# Morpheus_conector.net
KiCad netlist of a schematic drawn in Altium Designer
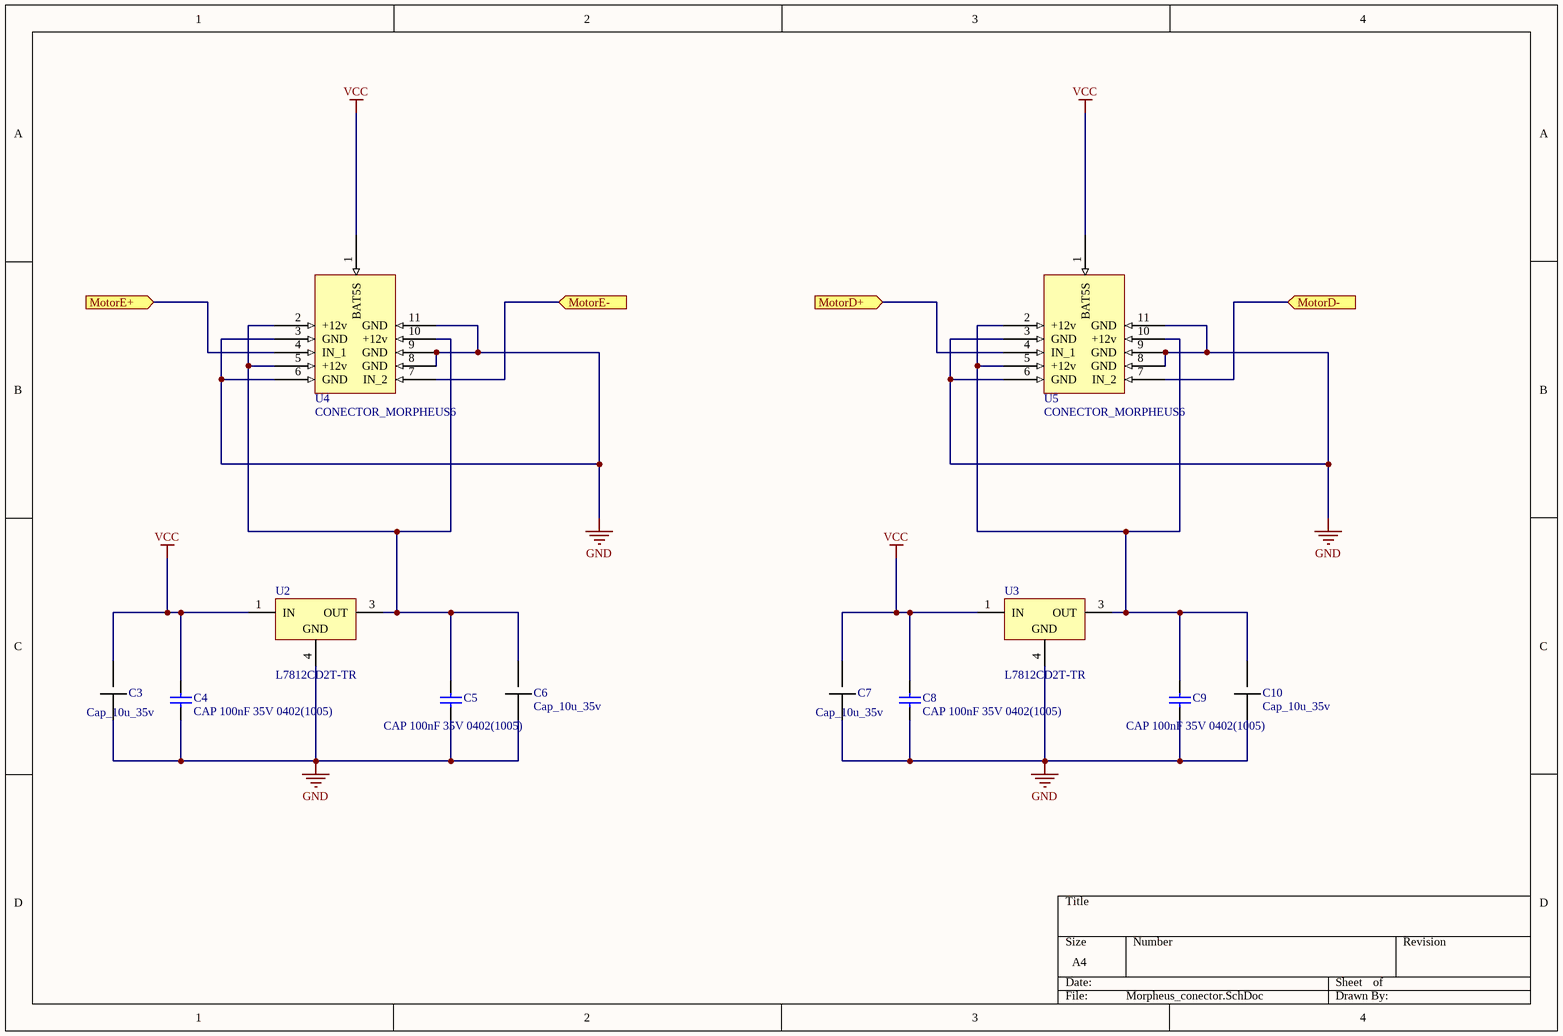
[diagram p0: Morpheus_conector.SchDoc]

(export (version "E")
  (design (tool "Eeschema 10.0.6"))
  (components
    (comp (ref "C3")
      (value "Cap_10u_35v")
      (footprint "Passives:CAP POL 2917/7343")
      (description "80-T491D106M35AT7280")
      (libsource (lib "LibSanhaço2017") (part "Cap_10u_35v"))
    )
    (comp (ref "C4")
      (value "CAP 100nF 35V 0402(1005)")
      (footprint "CAPC0402(1005)60_N")
      (fields (field (name "TOLERANCE") "Â±20%"))
      (libsource (lib "CAP 0402 100nF 35V") (part "CMP-1034-02076-1"))
    )
    (comp (ref "C5")
      (value "CAP 100nF 35V 0402(1005)")
      (footprint "CAPC0402(1005)60_N")
      (fields (field (name "TOLERANCE") "Â±20%"))
      (libsource (lib "CAP 0402 100nF 35V") (part "CMP-1034-02076-1"))
    )
    (comp (ref "C6")
      (value "Cap_10u_35v")
      (footprint "Passives:CAP POL 2917/7343")
      (description "80-T491D106M35AT7280")
      (libsource (lib "LibSanhaço2017") (part "Cap_10u_35v"))
    )
    (comp (ref "C7")
      (value "Cap_10u_35v")
      (footprint "Passives:CAP POL 2917/7343")
      (description "80-T491D106M35AT7280")
      (libsource (lib "LibSanhaço2017") (part "Cap_10u_35v"))
    )
    (comp (ref "C8")
      (value "CAP 100nF 35V 0402(1005)")
      (footprint "CAPC0402(1005)60_N")
      (fields (field (name "TOLERANCE") "Â±20%"))
      (libsource (lib "CAP 0402 100nF 35V") (part "CMP-1034-02076-1"))
    )
    (comp (ref "C9")
      (value "CAP 100nF 35V 0402(1005)")
      (footprint "CAPC0402(1005)60_N")
      (fields (field (name "TOLERANCE") "Â±20%"))
      (libsource (lib "CAP 0402 100nF 35V") (part "CMP-1034-02076-1"))
    )
    (comp (ref "C10")
      (value "Cap_10u_35v")
      (footprint "Passives:CAP POL 2917/7343")
      (description "80-T491D106M35AT7280")
      (libsource (lib "LibSanhaço2017") (part "Cap_10u_35v"))
    )
    (comp (ref "U2")
      (value "L7812CD2T-TR")
      (footprint "TO-263_N")
      (description "Positive Voltage Regulator, 3-Pin D2PAK, Tape and Reel")
      (libsource (lib "L7812CD2T-TR") (part "CMP-0244-00182-1"))
    )
    (comp (ref "U3")
      (value "L7812CD2T-TR")
      (footprint "TO-263_N")
      (description "Positive Voltage Regulator, 3-Pin D2PAK, Tape and Reel")
      (libsource (lib "L7812CD2T-TR") (part "CMP-0244-00182-1"))
    )
    (comp (ref "U4")
      (value "CONECTOR_MORPHEUS6")
      (libsource (lib "Morpheus_CONECTOR") (part "CONECTOR_MORPHEUS6"))
    )
    (comp (ref "U5")
      (value "CONECTOR_MORPHEUS6")
      (libsource (lib "Morpheus_CONECTOR") (part "CONECTOR_MORPHEUS6"))
    )
  )
  (nets
    (net (code "1") (name "/MotorD+") (class "Default")
      (node (ref "U5") (pin "4") (pinfunction "IN_1_4") (pintype "input"))
    )
    (net (code "2") (name "/MotorD-") (class "Default")
      (node (ref "U5") (pin "7") (pinfunction "IN_2_7") (pintype "input"))
    )
    (net (code "3") (name "/MotorE+") (class "Default")
      (node (ref "U4") (pin "4") (pinfunction "IN_1_4") (pintype "input"))
    )
    (net (code "4") (name "/MotorE-") (class "Default")
      (node (ref "U4") (pin "7") (pinfunction "IN_2_7") (pintype "input"))
    )
    (net (code "5") (name "GND") (class "Default")
      (node (ref "C10") (pin "1") (pinfunction "1_1") (pintype "passive"))
      (node (ref "C3") (pin "1") (pinfunction "1_1") (pintype "passive"))
      (node (ref "C4") (pin "1") (pinfunction "1_1") (pintype "passive"))
      (node (ref "C5") (pin "1") (pinfunction "1_1") (pintype "passive"))
      (node (ref "C6") (pin "1") (pinfunction "1_1") (pintype "passive"))
      (node (ref "C7") (pin "1") (pinfunction "1_1") (pintype "passive"))
      (node (ref "C8") (pin "1") (pinfunction "1_1") (pintype "passive"))
      (node (ref "C9") (pin "1") (pinfunction "1_1") (pintype "passive"))
      (node (ref "U2") (pin "4") (pinfunction "GND_4") (pintype "power_in"))
      (node (ref "U3") (pin "4") (pinfunction "GND_4") (pintype "power_in"))
      (node (ref "U4") (pin "11") (pinfunction "GND_11") (pintype "input"))
      (node (ref "U4") (pin "3") (pinfunction "GND_3") (pintype "input"))
      (node (ref "U4") (pin "6") (pinfunction "GND_6") (pintype "input"))
      (node (ref "U4") (pin "8") (pinfunction "GND_8") (pintype "input"))
      (node (ref "U4") (pin "9") (pinfunction "GND_9") (pintype "input"))
      (node (ref "U5") (pin "11") (pinfunction "GND_11") (pintype "input"))
      (node (ref "U5") (pin "3") (pinfunction "GND_3") (pintype "input"))
      (node (ref "U5") (pin "6") (pinfunction "GND_6") (pintype "input"))
      (node (ref "U5") (pin "8") (pinfunction "GND_8") (pintype "input"))
      (node (ref "U5") (pin "9") (pinfunction "GND_9") (pintype "input"))
    )
    (net (code "6") (name "Net-(U2-OUT)") (class "Default")
      (node (ref "C5") (pin "2") (pinfunction "2_2") (pintype "passive"))
      (node (ref "C6") (pin "2") (pinfunction "2_2") (pintype "passive"))
      (node (ref "U2") (pin "3") (pinfunction "OUT_3") (pintype "power_in"))
      (node (ref "U4") (pin "10") (pinfunction "+12v_10") (pintype "input"))
      (node (ref "U4") (pin "2") (pinfunction "+12v_2") (pintype "input"))
      (node (ref "U4") (pin "5") (pinfunction "+12v_5") (pintype "input"))
    )
    (net (code "7") (name "Net-(U3-OUT)") (class "Default")
      (node (ref "C10") (pin "2") (pinfunction "2_2") (pintype "passive"))
      (node (ref "C9") (pin "2") (pinfunction "2_2") (pintype "passive"))
      (node (ref "U3") (pin "3") (pinfunction "OUT_3") (pintype "power_in"))
      (node (ref "U5") (pin "10") (pinfunction "+12v_10") (pintype "input"))
      (node (ref "U5") (pin "2") (pinfunction "+12v_2") (pintype "input"))
      (node (ref "U5") (pin "5") (pinfunction "+12v_5") (pintype "input"))
    )
    (net (code "8") (name "VCC") (class "Default")
      (node (ref "C3") (pin "2") (pinfunction "2_2") (pintype "passive"))
      (node (ref "C4") (pin "2") (pinfunction "2_2") (pintype "passive"))
      (node (ref "C7") (pin "2") (pinfunction "2_2") (pintype "passive"))
      (node (ref "C8") (pin "2") (pinfunction "2_2") (pintype "passive"))
      (node (ref "U2") (pin "1") (pinfunction "IN_1") (pintype "power_in"))
      (node (ref "U3") (pin "1") (pinfunction "IN_1") (pintype "power_in"))
      (node (ref "U4") (pin "1") (pinfunction "BAT5S_1") (pintype "input"))
      (node (ref "U5") (pin "1") (pinfunction "BAT5S_1") (pintype "input"))
    )
  )
)
